# board3.net
KiCad netlist of a schematic drawn in EAGLE
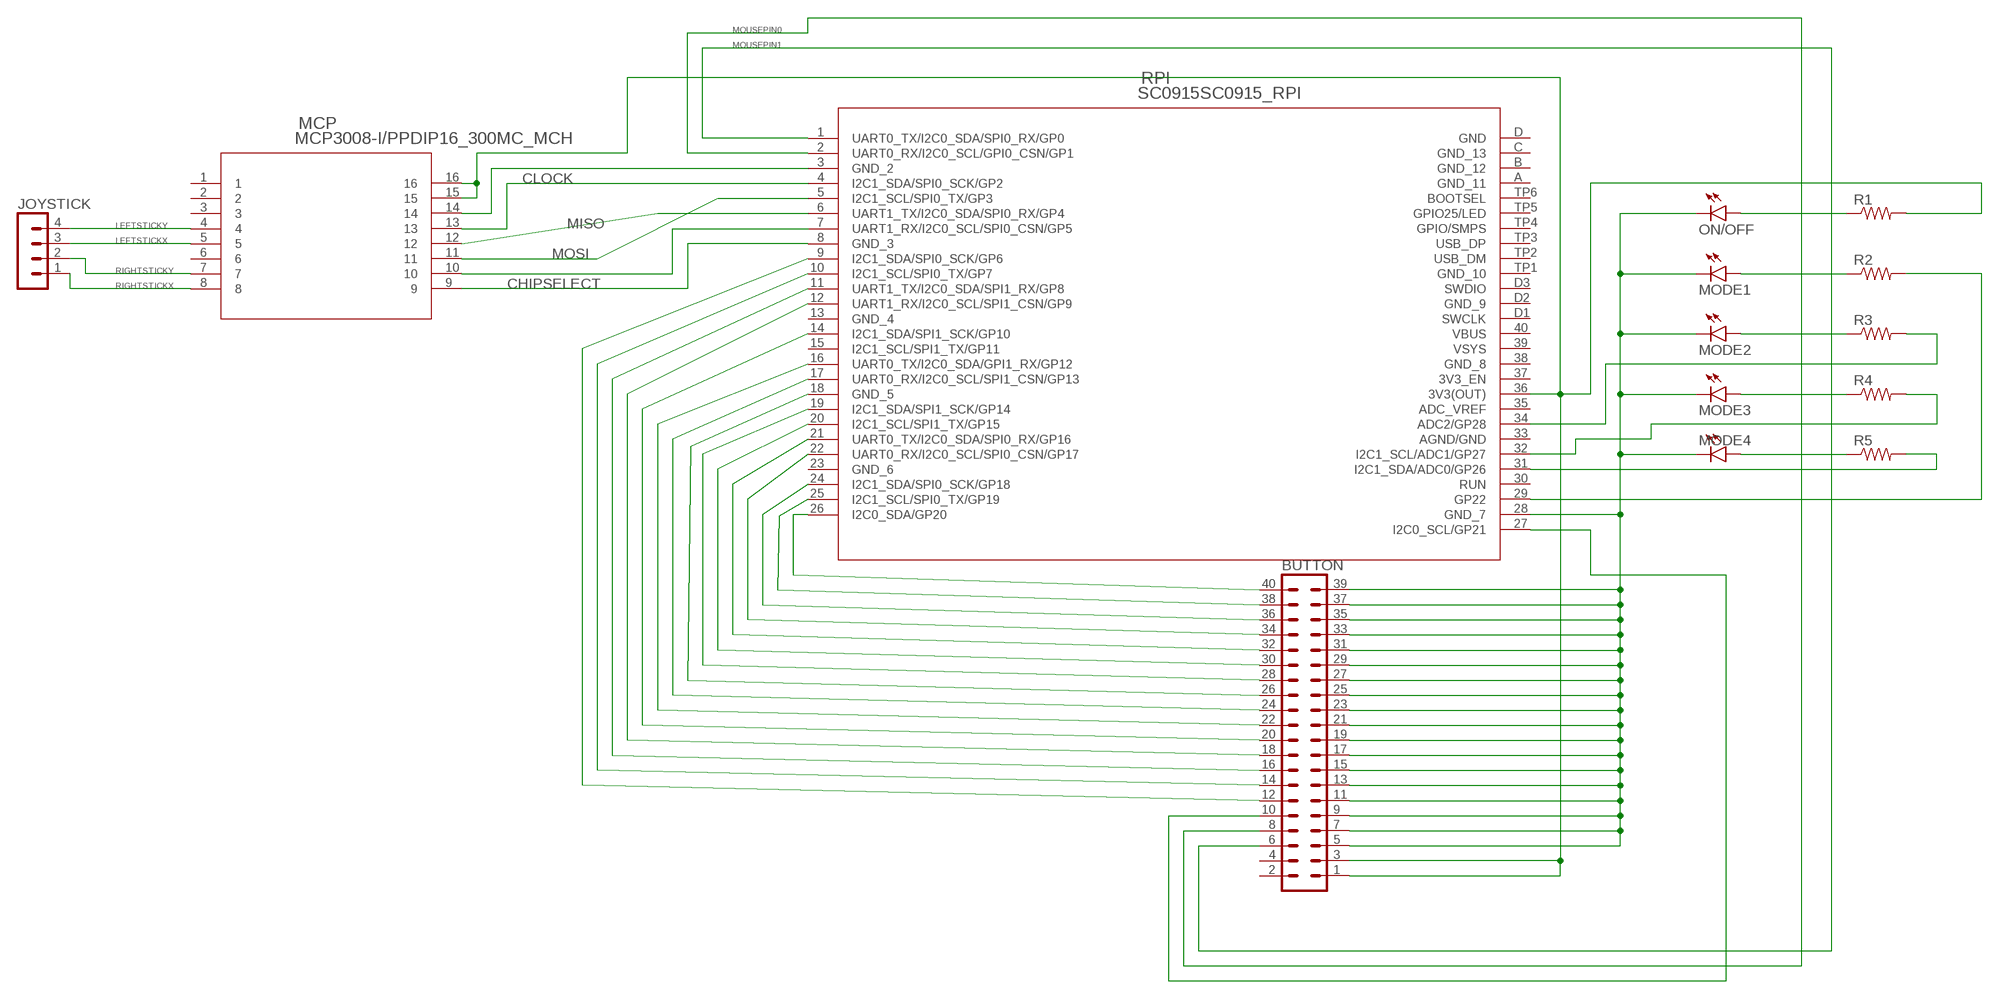
[diagram p0: schematic, sheet 1]

(export (version "E")
  (design (tool "Eeschema 10.0.6"))
  (components
    (comp (ref "BUTTON")
      (value "MA20-2")
      (footprint "eagle-import:MA20-2")
      (libsource (lib "eagle-import") (part "MA20-2"))
    )
    (comp (ref "JOYSTICK")
      (value "MA04-1")
      (footprint "eagle-import:MA04-1")
      (libsource (lib "eagle-import") (part "MA04-1"))
    )
    (comp (ref "MCP")
      (value "MCP3008-I/PPDIP16_300MC_MCH")
      (footprint "eagle-import:PDIP16_300MC_MCH")
      (fields
        (field (name "MANUFACTURER_PART_NUMBER") "MCP3008-I/P")
        (field (name "COPYRIGHT") "Copyright (C) 2022 Ultra Librarian. All rights reserved.")
      )
      (libsource (lib "eagle-import") (part "MCP3008-I/PPDIP16_300MC_MCH"))
    )
    (comp (ref "MODE1")
      (value "LED5MM")
      (footprint "eagle-import:LED5MM")
      (libsource (lib "eagle-import") (part "LED5MM"))
    )
    (comp (ref "MODE2")
      (value "LED5MM")
      (footprint "eagle-import:LED5MM")
      (libsource (lib "eagle-import") (part "LED5MM"))
    )
    (comp (ref "MODE3")
      (value "LED5MM")
      (footprint "eagle-import:LED5MM")
      (libsource (lib "eagle-import") (part "LED5MM"))
    )
    (comp (ref "MODE4")
      (value "LED5MM")
      (footprint "eagle-import:LED5MM")
      (libsource (lib "eagle-import") (part "LED5MM"))
    )
    (comp (ref "ON/OFF")
      (value "LED5MM")
      (footprint "eagle-import:LED5MM")
      (libsource (lib "eagle-import") (part "LED5MM"))
    )
    (comp (ref "R1")
      (value "R-US_0617/17")
      (footprint "eagle-import:0617_17")
      (libsource (lib "eagle-import") (part "R-US_0617/17"))
    )
    (comp (ref "R2")
      (value "R-US_0617/17")
      (footprint "eagle-import:0617_17")
      (libsource (lib "eagle-import") (part "R-US_0617/17"))
    )
    (comp (ref "R3")
      (value "R-US_0617/17")
      (footprint "eagle-import:0617_17")
      (libsource (lib "eagle-import") (part "R-US_0617/17"))
    )
    (comp (ref "R4")
      (value "R-US_0617/17")
      (footprint "eagle-import:0617_17")
      (libsource (lib "eagle-import") (part "R-US_0617/17"))
    )
    (comp (ref "R5")
      (value "R-US_0617/17")
      (footprint "eagle-import:0617_17")
      (libsource (lib "eagle-import") (part "R-US_0617/17"))
    )
    (comp (ref "RPI")
      (value "SC0915SC0915_RPI")
      (footprint "eagle-import:SC0915_RPI")
      (fields
        (field (name "MANUFACTURER_PART_NUMBER") "SC0915")
        (field (name "COPYRIGHT") "Copyright (C) 2022 Ultra Librarian. All rights reserved.")
      )
      (libsource (lib "eagle-import") (part "SC0915SC0915_RPI"))
    )
  )
  (nets
    (net (code "1") (name "/3V3_EN") (class "Default")
      (node (ref "RPI") (pin "37") (pinfunction "3V3_EN_37") (pintype "power_in"))
    )
    (net (code "2") (name "/ADC_VREF") (class "Default")
      (node (ref "RPI") (pin "35") (pinfunction "ADC_VREF_35") (pintype "power_in"))
    )
    (net (code "3") (name "/CHIPSELECT") (class "Default")
      (node (ref "MCP") (pin "10") (pinfunction "10_10") (pintype "passive"))
      (node (ref "RPI") (pin "7") (pinfunction "UART1_RX/I2C0_SCL/SPI0_CSN/GP5_7") (pintype "bidirectional"))
    )
    (net (code "4") (name "/CLOCK") (class "Default")
      (node (ref "MCP") (pin "13") (pinfunction "13_13") (pintype "passive"))
      (node (ref "RPI") (pin "4") (pinfunction "I2C1_SDA/SPI0_SCK/GP2_4") (pintype "bidirectional"))
    )
    (net (code "5") (name "/LEFTSTICKX") (class "Default")
      (node (ref "JOYSTICK") (pin "3") (pinfunction "3_3") (pintype "passive"))
      (node (ref "MCP") (pin "5") (pinfunction "5_5") (pintype "passive"))
    )
    (net (code "6") (name "/LEFTSTICKY") (class "Default")
      (node (ref "JOYSTICK") (pin "4") (pinfunction "4_4") (pintype "passive"))
      (node (ref "MCP") (pin "4") (pinfunction "4_4") (pintype "passive"))
    )
    (net (code "7") (name "/MISO") (class "Default")
      (node (ref "MCP") (pin "12") (pinfunction "12_12") (pintype "passive"))
      (node (ref "RPI") (pin "6") (pinfunction "UART1_TX/I2C0_SDA/SPI0_RX/GP4_6") (pintype "bidirectional"))
    )
    (net (code "8") (name "/MOSI") (class "Default")
      (node (ref "MCP") (pin "11") (pinfunction "11_11") (pintype "passive"))
      (node (ref "RPI") (pin "5") (pinfunction "I2C1_SCL/SPI0_TX/GP3_5") (pintype "bidirectional"))
    )
    (net (code "9") (name "/MOUSEPIN0") (class "Default")
      (node (ref "BUTTON") (pin "8") (pinfunction "8_8") (pintype "passive"))
      (node (ref "RPI") (pin "2") (pinfunction "UART0_RX/I2C0_SCL/GPI0_CSN/GP1_2") (pintype "bidirectional"))
    )
    (net (code "10") (name "/MOUSEPIN1") (class "Default")
      (node (ref "BUTTON") (pin "6") (pinfunction "6_6") (pintype "passive"))
      (node (ref "RPI") (pin "1") (pinfunction "UART0_TX/I2C0_SDA/SPI0_RX/GP0_1") (pintype "bidirectional"))
    )
    (net (code "11") (name "/RIGHTSTICKX") (class "Default")
      (node (ref "JOYSTICK") (pin "1") (pinfunction "1_1") (pintype "passive"))
      (node (ref "MCP") (pin "8") (pinfunction "8_8") (pintype "passive"))
    )
    (net (code "12") (name "/RIGHTSTICKY") (class "Default")
      (node (ref "JOYSTICK") (pin "2") (pinfunction "2_2") (pintype "passive"))
      (node (ref "MCP") (pin "7") (pinfunction "7_7") (pintype "passive"))
    )
    (net (code "13") (name "/VBUS") (class "Default")
      (node (ref "RPI") (pin "40") (pinfunction "VBUS_40") (pintype "power_in"))
    )
    (net (code "14") (name "/VSYS") (class "Default")
      (node (ref "RPI") (pin "39") (pinfunction "VSYS_39") (pintype "power_in"))
    )
    (net (code "15") (name "Net-(MODE1-C)") (class "Default")
      (node (ref "BUTTON") (pin "11") (pinfunction "11_11") (pintype "passive"))
      (node (ref "BUTTON") (pin "13") (pinfunction "13_13") (pintype "passive"))
      (node (ref "BUTTON") (pin "15") (pinfunction "15_15") (pintype "passive"))
      (node (ref "BUTTON") (pin "17") (pinfunction "17_17") (pintype "passive"))
      (node (ref "BUTTON") (pin "19") (pinfunction "19_19") (pintype "passive"))
      (node (ref "BUTTON") (pin "21") (pinfunction "21_21") (pintype "passive"))
      (node (ref "BUTTON") (pin "23") (pinfunction "23_23") (pintype "passive"))
      (node (ref "BUTTON") (pin "25") (pinfunction "25_25") (pintype "passive"))
      (node (ref "BUTTON") (pin "27") (pinfunction "27_27") (pintype "passive"))
      (node (ref "BUTTON") (pin "29") (pinfunction "29_29") (pintype "passive"))
      (node (ref "BUTTON") (pin "31") (pinfunction "31_31") (pintype "passive"))
      (node (ref "BUTTON") (pin "33") (pinfunction "33_33") (pintype "passive"))
      (node (ref "BUTTON") (pin "35") (pinfunction "35_35") (pintype "passive"))
      (node (ref "BUTTON") (pin "37") (pinfunction "37_37") (pintype "passive"))
      (node (ref "BUTTON") (pin "39") (pinfunction "39_39") (pintype "passive"))
      (node (ref "BUTTON") (pin "5") (pinfunction "5_5") (pintype "passive"))
      (node (ref "BUTTON") (pin "7") (pinfunction "7_7") (pintype "passive"))
      (node (ref "BUTTON") (pin "9") (pinfunction "9_9") (pintype "passive"))
      (node (ref "MODE1") (pin "K") (pinfunction "C_K") (pintype "passive"))
      (node (ref "MODE2") (pin "K") (pinfunction "C_K") (pintype "passive"))
      (node (ref "MODE3") (pin "K") (pinfunction "C_K") (pintype "passive"))
      (node (ref "MODE4") (pin "K") (pinfunction "C_K") (pintype "passive"))
      (node (ref "ON/OFF") (pin "K") (pinfunction "C_K") (pintype "passive"))
      (node (ref "RPI") (pin "28") (pinfunction "GND_7_28") (pintype "passive"))
    )
    (net (code "16") (name "Net-(MODE1-PadA)") (class "Default")
      (node (ref "MODE1") (pin "A") (pinfunction "A_A") (pintype "passive"))
      (node (ref "R2") (pin "1") (pinfunction "1_1") (pintype "passive"))
    )
    (net (code "17") (name "Net-(MODE2-PadA)") (class "Default")
      (node (ref "MODE2") (pin "A") (pinfunction "A_A") (pintype "passive"))
      (node (ref "R3") (pin "1") (pinfunction "1_1") (pintype "passive"))
    )
    (net (code "18") (name "Net-(MODE3-PadA)") (class "Default")
      (node (ref "MODE3") (pin "A") (pinfunction "A_A") (pintype "passive"))
      (node (ref "R4") (pin "1") (pinfunction "1_1") (pintype "passive"))
    )
    (net (code "19") (name "Net-(MODE4-PadA)") (class "Default")
      (node (ref "MODE4") (pin "A") (pinfunction "A_A") (pintype "passive"))
      (node (ref "R5") (pin "1") (pinfunction "1_1") (pintype "passive"))
    )
    (net (code "20") (name "Net-(ON/OFF-PadA)") (class "Default")
      (node (ref "ON/OFF") (pin "A") (pinfunction "A_A") (pintype "passive"))
      (node (ref "R1") (pin "1") (pinfunction "1_1") (pintype "passive"))
    )
    (net (code "21") (name "Net-(RPI-3V3(OUT))") (class "Default")
      (node (ref "BUTTON") (pin "1") (pinfunction "1_1") (pintype "passive"))
      (node (ref "BUTTON") (pin "3") (pinfunction "3_3") (pintype "passive"))
      (node (ref "MCP") (pin "15") (pinfunction "15_15") (pintype "passive"))
      (node (ref "MCP") (pin "16") (pinfunction "16_16") (pintype "passive"))
      (node (ref "R1") (pin "2") (pinfunction "2_2") (pintype "passive"))
      (node (ref "RPI") (pin "36") (pinfunction "3V3(OUT)_36") (pintype "output"))
    )
    (net (code "22") (name "Net-(RPI-ADC2{slash}GP28)") (class "Default")
      (node (ref "R3") (pin "2") (pinfunction "2_2") (pintype "passive"))
      (node (ref "RPI") (pin "34") (pinfunction "ADC2/GP28_34") (pintype "bidirectional"))
    )
    (net (code "23") (name "Net-(RPI-GND_2)") (class "Default")
      (node (ref "MCP") (pin "14") (pinfunction "14_14") (pintype "passive"))
      (node (ref "RPI") (pin "3") (pinfunction "GND_2_3") (pintype "passive"))
    )
    (net (code "24") (name "Net-(RPI-GND_3)") (class "Default")
      (node (ref "MCP") (pin "9") (pinfunction "9_9") (pintype "passive"))
      (node (ref "RPI") (pin "8") (pinfunction "GND_3_8") (pintype "passive"))
    )
    (net (code "25") (name "Net-(RPI-GND_5)") (class "Default")
      (node (ref "BUTTON") (pin "26") (pinfunction "26_26") (pintype "passive"))
      (node (ref "RPI") (pin "18") (pinfunction "GND_5_18") (pintype "passive"))
    )
    (net (code "26") (name "Net-(RPI-GP22)") (class "Default")
      (node (ref "R2") (pin "2") (pinfunction "2_2") (pintype "passive"))
      (node (ref "RPI") (pin "29") (pinfunction "GP22_29") (pintype "bidirectional"))
    )
    (net (code "27") (name "Net-(RPI-I2C0_SCL{slash}GP21)") (class "Default")
      (node (ref "BUTTON") (pin "10") (pinfunction "10_10") (pintype "passive"))
      (node (ref "RPI") (pin "27") (pinfunction "I2C0_SCL/GP21_27") (pintype "bidirectional"))
    )
    (net (code "28") (name "Net-(RPI-I2C0_SDA{slash}GP20)") (class "Default")
      (node (ref "BUTTON") (pin "40") (pinfunction "40_40") (pintype "passive"))
      (node (ref "RPI") (pin "26") (pinfunction "I2C0_SDA/GP20_26") (pintype "bidirectional"))
    )
    (net (code "29") (name "Net-(RPI-I2C1_SCL{slash}ADC1{slash}GP27)") (class "Default")
      (node (ref "R4") (pin "2") (pinfunction "2_2") (pintype "passive"))
      (node (ref "RPI") (pin "32") (pinfunction "I2C1_SCL/ADC1/GP27_32") (pintype "bidirectional"))
    )
    (net (code "30") (name "Net-(RPI-I2C1_SCL{slash}SPI0_TX{slash}GP7)") (class "Default")
      (node (ref "BUTTON") (pin "14") (pinfunction "14_14") (pintype "passive"))
      (node (ref "RPI") (pin "10") (pinfunction "I2C1_SCL/SPI0_TX/GP7_10") (pintype "bidirectional"))
    )
    (net (code "31") (name "Net-(RPI-I2C1_SCL{slash}SPI0_TX{slash}GP19)") (class "Default")
      (node (ref "BUTTON") (pin "38") (pinfunction "38_38") (pintype "passive"))
      (node (ref "RPI") (pin "25") (pinfunction "I2C1_SCL/SPI0_TX/GP19_25") (pintype "bidirectional"))
    )
    (net (code "32") (name "Net-(RPI-I2C1_SCL{slash}SPI1_TX{slash}GP15)") (class "Default")
      (node (ref "BUTTON") (pin "30") (pinfunction "30_30") (pintype "passive"))
      (node (ref "RPI") (pin "20") (pinfunction "I2C1_SCL/SPI1_TX/GP15_20") (pintype "bidirectional"))
    )
    (net (code "33") (name "Net-(RPI-I2C1_SDA{slash}ADC0{slash}GP26)") (class "Default")
      (node (ref "R5") (pin "2") (pinfunction "2_2") (pintype "passive"))
      (node (ref "RPI") (pin "31") (pinfunction "I2C1_SDA/ADC0/GP26_31") (pintype "bidirectional"))
    )
    (net (code "34") (name "Net-(RPI-I2C1_SDA{slash}SPI0_SCK{slash}GP6)") (class "Default")
      (node (ref "BUTTON") (pin "12") (pinfunction "12_12") (pintype "passive"))
      (node (ref "RPI") (pin "9") (pinfunction "I2C1_SDA/SPI0_SCK/GP6_9") (pintype "bidirectional"))
    )
    (net (code "35") (name "Net-(RPI-I2C1_SDA{slash}SPI0_SCK{slash}GP18)") (class "Default")
      (node (ref "BUTTON") (pin "36") (pinfunction "36_36") (pintype "passive"))
      (node (ref "RPI") (pin "24") (pinfunction "I2C1_SDA/SPI0_SCK/GP18_24") (pintype "bidirectional"))
    )
    (net (code "36") (name "Net-(RPI-I2C1_SDA{slash}SPI1_SCK{slash}GP10)") (class "Default")
      (node (ref "BUTTON") (pin "20") (pinfunction "20_20") (pintype "passive"))
      (node (ref "RPI") (pin "14") (pinfunction "I2C1_SDA/SPI1_SCK/GP10_14") (pintype "bidirectional"))
    )
    (net (code "37") (name "Net-(RPI-I2C1_SDA{slash}SPI1_SCK{slash}GP14)") (class "Default")
      (node (ref "BUTTON") (pin "28") (pinfunction "28_28") (pintype "passive"))
      (node (ref "RPI") (pin "19") (pinfunction "I2C1_SDA/SPI1_SCK/GP14_19") (pintype "bidirectional"))
    )
    (net (code "38") (name "Net-(RPI-UART0_RX{slash}I2C0_SCL{slash}SPI0_CSN{slash}GP17)") (class "Default")
      (node (ref "BUTTON") (pin "34") (pinfunction "34_34") (pintype "passive"))
      (node (ref "RPI") (pin "22") (pinfunction "UART0_RX/I2C0_SCL/SPI0_CSN/GP17_22") (pintype "bidirectional"))
    )
    (net (code "39") (name "Net-(RPI-UART0_RX{slash}I2C0_SCL{slash}SPI1_CSN{slash}GP13)") (class "Default")
      (node (ref "BUTTON") (pin "24") (pinfunction "24_24") (pintype "passive"))
      (node (ref "RPI") (pin "17") (pinfunction "UART0_RX/I2C0_SCL/SPI1_CSN/GP13_17") (pintype "bidirectional"))
    )
    (net (code "40") (name "Net-(RPI-UART0_TX{slash}I2C0_SDA{slash}GPI1_RX{slash}GP12)") (class "Default")
      (node (ref "BUTTON") (pin "22") (pinfunction "22_22") (pintype "passive"))
      (node (ref "RPI") (pin "16") (pinfunction "UART0_TX/I2C0_SDA/GPI1_RX/GP12_16") (pintype "bidirectional"))
    )
    (net (code "41") (name "Net-(RPI-UART0_TX{slash}I2C0_SDA{slash}SPI0_RX{slash}GP16)") (class "Default")
      (node (ref "BUTTON") (pin "32") (pinfunction "32_32") (pintype "passive"))
      (node (ref "RPI") (pin "21") (pinfunction "UART0_TX/I2C0_SDA/SPI0_RX/GP16_21") (pintype "bidirectional"))
    )
    (net (code "42") (name "Net-(RPI-UART1_RX{slash}I2C0_SCL{slash}SPI1_CSN{slash}GP9)") (class "Default")
      (node (ref "BUTTON") (pin "18") (pinfunction "18_18") (pintype "passive"))
      (node (ref "RPI") (pin "12") (pinfunction "UART1_RX/I2C0_SCL/SPI1_CSN/GP9_12") (pintype "bidirectional"))
    )
    (net (code "43") (name "Net-(RPI-UART1_TX{slash}I2C0_SDA{slash}SPI1_RX{slash}GP8)") (class "Default")
      (node (ref "BUTTON") (pin "16") (pinfunction "16_16") (pintype "passive"))
      (node (ref "RPI") (pin "11") (pinfunction "UART1_TX/I2C0_SDA/SPI1_RX/GP8_11") (pintype "bidirectional"))
    )
    (net (code "44") (name "unconnected-(BUTTON-Pad2)") (class "Default")
      (node (ref "BUTTON") (pin "2") (pinfunction "2_2") (pintype "passive"))
    )
    (net (code "45") (name "unconnected-(BUTTON-Pad4)") (class "Default")
      (node (ref "BUTTON") (pin "4") (pinfunction "4_4") (pintype "passive"))
    )
    (net (code "46") (name "unconnected-(MCP-Pad1)") (class "Default")
      (node (ref "MCP") (pin "1") (pinfunction "1_1") (pintype "passive"))
    )
    (net (code "47") (name "unconnected-(MCP-Pad2)") (class "Default")
      (node (ref "MCP") (pin "2") (pinfunction "2_2") (pintype "passive"))
    )
    (net (code "48") (name "unconnected-(MCP-Pad3)") (class "Default")
      (node (ref "MCP") (pin "3") (pinfunction "3_3") (pintype "passive"))
    )
    (net (code "49") (name "unconnected-(MCP-Pad6)") (class "Default")
      (node (ref "MCP") (pin "6") (pinfunction "6_6") (pintype "passive"))
    )
    (net (code "50") (name "unconnected-(RPI-AGND{slash}GND-Pad33)") (class "Default")
      (node (ref "RPI") (pin "33") (pinfunction "AGND/GND_33") (pintype "passive"))
    )
    (net (code "51") (name "unconnected-(RPI-BOOTSEL-PadTP6)") (class "Default")
      (node (ref "RPI") (pin "TP6") (pinfunction "BOOTSEL_TP6") (pintype "passive"))
    )
    (net (code "52") (name "unconnected-(RPI-GND-PadD)") (class "Default")
      (node (ref "RPI") (pin "D") (pinfunction "GND_D") (pintype "passive"))
    )
    (net (code "53") (name "unconnected-(RPI-GND_4-Pad13)") (class "Default")
      (node (ref "RPI") (pin "13") (pinfunction "GND_4_13") (pintype "passive"))
    )
    (net (code "54") (name "unconnected-(RPI-GND_6-Pad23)") (class "Default")
      (node (ref "RPI") (pin "23") (pinfunction "GND_6_23") (pintype "passive"))
    )
    (net (code "55") (name "unconnected-(RPI-GND_8-Pad38)") (class "Default")
      (node (ref "RPI") (pin "38") (pinfunction "GND_8_38") (pintype "passive"))
    )
    (net (code "56") (name "unconnected-(RPI-GND_9-PadD2)") (class "Default")
      (node (ref "RPI") (pin "D2") (pinfunction "GND_9_D2") (pintype "passive"))
    )
    (net (code "57") (name "unconnected-(RPI-GND_10-PadTP1)") (class "Default")
      (node (ref "RPI") (pin "TP1") (pinfunction "GND_10_TP1") (pintype "passive"))
    )
    (net (code "58") (name "unconnected-(RPI-GND_11-PadA)") (class "Default")
      (node (ref "RPI") (pin "A") (pinfunction "GND_11_A") (pintype "passive"))
    )
    (net (code "59") (name "unconnected-(RPI-GND_12-PadB)") (class "Default")
      (node (ref "RPI") (pin "B") (pinfunction "GND_12_B") (pintype "passive"))
    )
    (net (code "60") (name "unconnected-(RPI-GND_13-PadC)") (class "Default")
      (node (ref "RPI") (pin "C") (pinfunction "GND_13_C") (pintype "passive"))
    )
    (net (code "61") (name "unconnected-(RPI-GPIO25{slash}LED-PadTP5)") (class "Default")
      (node (ref "RPI") (pin "TP5") (pinfunction "GPIO25/LED_TP5") (pintype "passive"))
    )
    (net (code "62") (name "unconnected-(RPI-GPIO{slash}SMPS-PadTP4)") (class "Default")
      (node (ref "RPI") (pin "TP4") (pinfunction "GPIO/SMPS_TP4") (pintype "passive"))
    )
    (net (code "63") (name "unconnected-(RPI-I2C1_SCL{slash}SPI1_TX{slash}GP11-Pad15)") (class "Default")
      (node (ref "RPI") (pin "15") (pinfunction "I2C1_SCL/SPI1_TX/GP11_15") (pintype "bidirectional"))
    )
    (net (code "64") (name "unconnected-(RPI-RUN-Pad30)") (class "Default")
      (node (ref "RPI") (pin "30") (pinfunction "RUN_30") (pintype "passive"))
    )
    (net (code "65") (name "unconnected-(RPI-SWCLK-PadD1)") (class "Default")
      (node (ref "RPI") (pin "D1") (pinfunction "SWCLK_D1") (pintype "passive"))
    )
    (net (code "66") (name "unconnected-(RPI-SWDIO-PadD3)") (class "Default")
      (node (ref "RPI") (pin "D3") (pinfunction "SWDIO_D3") (pintype "passive"))
    )
    (net (code "67") (name "unconnected-(RPI-USB_DM-PadTP2)") (class "Default")
      (node (ref "RPI") (pin "TP2") (pinfunction "USB_DM_TP2") (pintype "passive"))
    )
    (net (code "68") (name "unconnected-(RPI-USB_DP-PadTP3)") (class "Default")
      (node (ref "RPI") (pin "TP3") (pinfunction "USB_DP_TP3") (pintype "passive"))
    )
  )
)
